# V1_0.net
KiCad netlist of a schematic drawn in Altium Designer
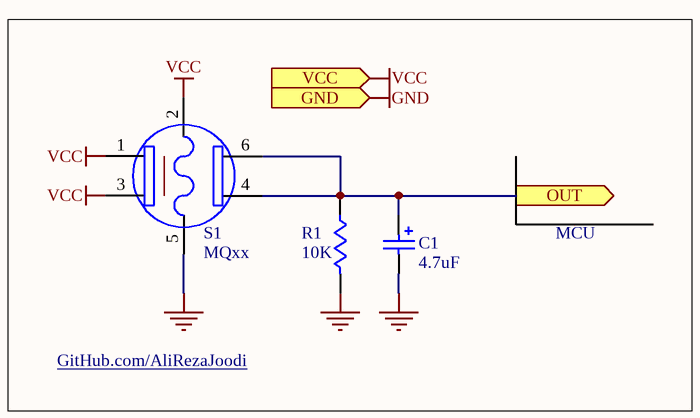
[diagram p0: V1.0.SchDoc]

(export (version "E")
  (design (tool "Eeschema 10.0.6"))
  (components
    (comp (ref "C1")
      (value "4.7uF")
      (footprint "CAPPR2.5-6.3x5")
      (description "Polarized Capacitor (Radial)")
      (fields
        (field (name "MANUFACTURER") "Generic Components")
        (field (name "Comment") "Cap Pol1")
        (field (name "PUBLISHER") "Altium Limited")
      )
      (libsource (lib "Miscellaneous Devices") (part "Cap Pol1"))
    )
    (comp (ref "R1")
      (value "10K")
      (footprint "AXIAL-0.4")
      (description "Resistor")
      (fields
        (field (name "MANUFACTURER") "Generic Components")
        (field (name "Comment") "Res1")
        (field (name "PUBLISHER") "Altium Limited")
      )
      (libsource (lib "Miscellaneous Devices") (part "Res1"))
    )
    (comp (ref "S1")
      (value "MQxx")
      (footprint "MQxx")
      (description "Gas Sensor")
      (fields (field (name "MANUFACTURER") "Generic Components") (field (name "PUBLISHER") "Altium Limited"))
      (libsource (lib "Miscellaneous Devices") (part "MQ"))
    )
  )
  (nets
    (net (code "1") (name "/OUT") (class "Default")
      (node (ref "C1") (pin "1") (pinfunction "1_1") (pintype "passive"))
      (node (ref "R1") (pin "1") (pinfunction "1_1") (pintype "passive"))
      (node (ref "S1") (pin "4") (pinfunction "33_4") (pintype "passive"))
      (node (ref "S1") (pin "6") (pinfunction "6_6") (pintype "passive"))
    )
    (net (code "2") (name "GND") (class "Default")
      (node (ref "C1") (pin "2") (pinfunction "2_2") (pintype "passive"))
      (node (ref "R1") (pin "2") (pinfunction "2_2") (pintype "passive"))
      (node (ref "S1") (pin "5") (pinfunction "5_5") (pintype "passive"))
    )
    (net (code "3") (name "VCC") (class "Default")
      (node (ref "S1") (pin "1") (pinfunction "31_1") (pintype "passive"))
      (node (ref "S1") (pin "2") (pinfunction "2_2") (pintype "passive"))
      (node (ref "S1") (pin "3") (pinfunction "3_3") (pintype "passive"))
    )
  )
)
